# HHC.net
KiCad netlist of a schematic drawn in EAGLE
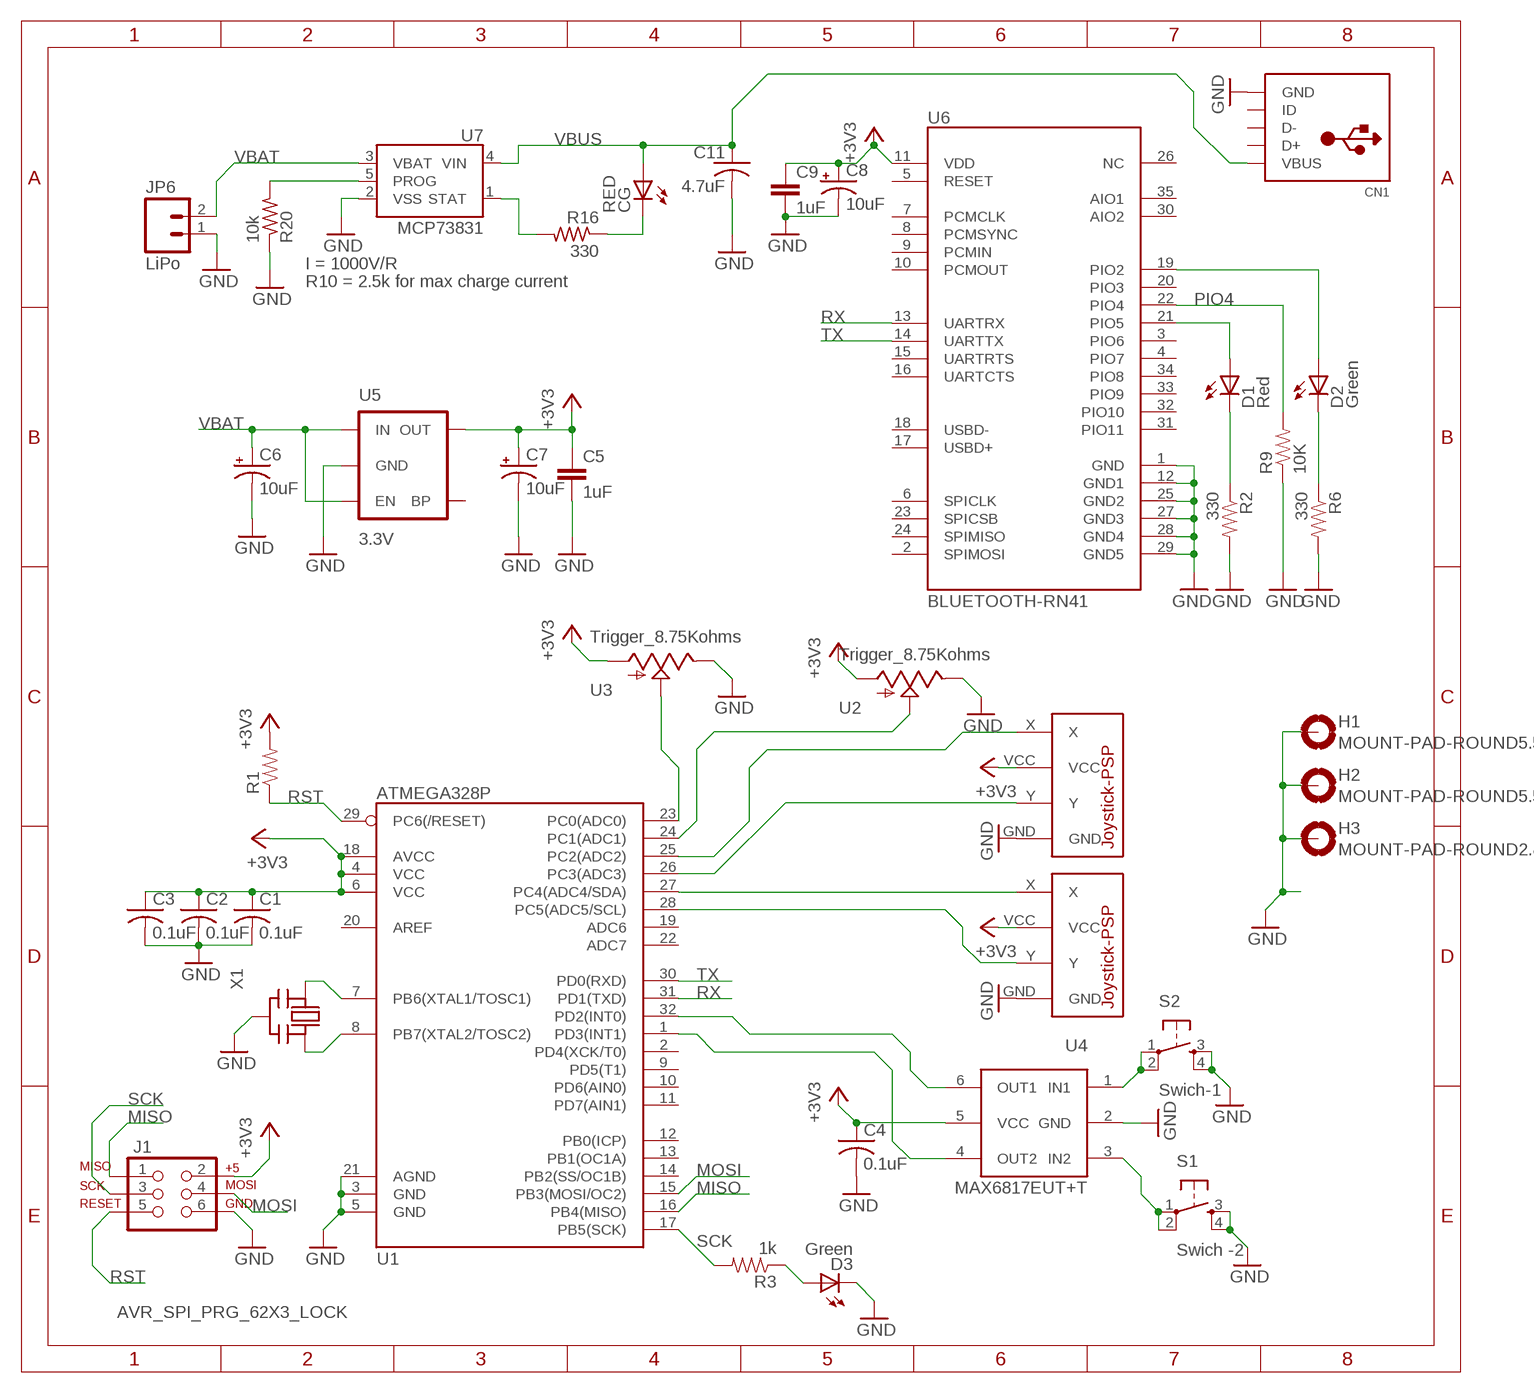
[diagram p0: schematic, sheet 1]

(export (version "E")
  (design (tool "Eeschema 10.0.6"))
  (components
    (comp (ref "C1")
      (value "0.1uF")
      (footprint "eagle-import:C0805")
      (libsource (lib "eagle-import") (part "C-USC0805"))
    )
    (comp (ref "C2")
      (value "0.1uF")
      (footprint "eagle-import:C0805")
      (libsource (lib "eagle-import") (part "C-USC0805"))
    )
    (comp (ref "C3")
      (value "0.1uF")
      (footprint "eagle-import:C0805")
      (libsource (lib "eagle-import") (part "C-USC0805"))
    )
    (comp (ref "C4")
      (value "0.1uF")
      (footprint "eagle-import:C0805")
      (libsource (lib "eagle-import") (part "C-USC0805"))
    )
    (comp (ref "C5")
      (value "1uF")
      (footprint "eagle-import:0805")
      (libsource (lib "eagle-import") (part "CAP0805"))
    )
    (comp (ref "C6")
      (value "10uF")
      (footprint "eagle-import:EIA3216")
      (libsource (lib "eagle-import") (part "CAP_POL1206"))
    )
    (comp (ref "C7")
      (value "10uF")
      (footprint "eagle-import:EIA3216")
      (libsource (lib "eagle-import") (part "CAP_POL1206"))
    )
    (comp (ref "C8")
      (value "10uF")
      (footprint "eagle-import:EIA3216")
      (libsource (lib "eagle-import") (part "CAP_POL1206"))
    )
    (comp (ref "C9")
      (value "1uF")
      (footprint "eagle-import:0805")
      (libsource (lib "eagle-import") (part "CAP0805"))
    )
    (comp (ref "C11")
      (value "4.7uF")
      (footprint "eagle-import:C0805")
      (libsource (lib "eagle-import") (part "resistor_C-USC0805"))
    )
    (comp (ref "CG")
      (value "RED")
      (footprint "eagle-import:SML0805")
      (libsource (lib "eagle-import") (part "LEDSML0805"))
    )
    (comp (ref "CN1")
      (value "USBMINIB")
      (footprint "eagle-import:USB-MINIB")
      (libsource (lib "eagle-import") (part "USBMINIB"))
    )
    (comp (ref "D1")
      (value "Red")
      (footprint "eagle-import:LED-0603")
      (libsource (lib "eagle-import") (part "LED0603"))
    )
    (comp (ref "D2")
      (value "Green")
      (footprint "eagle-import:LED-0603")
      (libsource (lib "eagle-import") (part "LED0603"))
    )
    (comp (ref "D3")
      (value "Green")
      (footprint "eagle-import:LED-0603")
      (libsource (lib "eagle-import") (part "LED0603"))
    )
    (comp (ref "H1")
      (value "MOUNT-PAD-ROUND5.5")
      (footprint "eagle-import:5,5-PAD")
      (libsource (lib "eagle-import") (part "MOUNT-PAD-ROUND5.5"))
    )
    (comp (ref "H2")
      (value "MOUNT-PAD-ROUND5.5")
      (footprint "eagle-import:5,5-PAD")
      (libsource (lib "eagle-import") (part "MOUNT-PAD-ROUND5.5"))
    )
    (comp (ref "H3")
      (value "MOUNT-PAD-ROUND2.8")
      (footprint "eagle-import:2,8-PAD")
      (libsource (lib "eagle-import") (part "MOUNT-PAD-ROUND2.8"))
    )
    (comp (ref "J1")
      (value "AVR_SPI_PRG_62X3_LOCK")
      (footprint "eagle-import:2X3_LOCK")
      (libsource (lib "eagle-import") (part "AVR_SPI_PRG_62X3_LOCK"))
    )
    (comp (ref "JP6")
      (value "LiPo")
      (footprint "eagle-import:JST-2-SMD")
      (libsource (lib "eagle-import") (part "M02-JST-2MM-SMT"))
    )
    (comp (ref "R1")
      (value "RESISTOR0805-RES")
      (footprint "eagle-import:0805")
      (libsource (lib "eagle-import") (part "SparkFun-Resistors_RESISTOR0805-RES"))
    )
    (comp (ref "R2")
      (value "330")
      (footprint "eagle-import:0805")
      (libsource (lib "eagle-import") (part "RESISTOR0805-RES"))
    )
    (comp (ref "R3")
      (value "1k")
      (footprint "eagle-import:0805")
      (libsource (lib "eagle-import") (part "SparkFun-Resistors_RESISTOR0805-RES"))
    )
    (comp (ref "R6")
      (value "330")
      (footprint "eagle-import:0805")
      (libsource (lib "eagle-import") (part "RESISTOR0805-RES"))
    )
    (comp (ref "R9")
      (value "10K")
      (footprint "eagle-import:0805")
      (libsource (lib "eagle-import") (part "RESISTOR0805-RES"))
    )
    (comp (ref "R16")
      (value "330")
      (footprint "eagle-import:R0805")
      (libsource (lib "eagle-import") (part "R-US_R0805"))
    )
    (comp (ref "R20")
      (value "10k")
      (footprint "eagle-import:R0805")
      (libsource (lib "eagle-import") (part "R-US_R0805"))
    )
    (comp (ref "S1")
      (value "Swich -2")
      (footprint "eagle-import:TACTILE-PTH")
      (libsource (lib "eagle-import") (part "TAC_SWITCHPTH"))
    )
    (comp (ref "S2")
      (value "Swich-1")
      (footprint "eagle-import:TACTILE-PTH")
      (libsource (lib "eagle-import") (part "TAC_SWITCHPTH"))
    )
    (comp (ref "U$1")
      (value "JOYSTICK-PSP1000")
      (footprint "eagle-import:JOYSTICK-PSP1000")
      (libsource (lib "eagle-import") (part "JOYSTICK-PSP1000"))
    )
    (comp (ref "U$2")
      (value "JOYSTICK-PSP1000")
      (footprint "eagle-import:JOYSTICK-PSP1000")
      (libsource (lib "eagle-import") (part "JOYSTICK-PSP1000"))
    )
    (comp (ref "U1")
      (value "ATMEGA328P")
      (footprint "eagle-import:TQFP32-08")
      (libsource (lib "eagle-import") (part "ATMEGA328_SMT"))
    )
    (comp (ref "U2")
      (value "TRIGGEREDGE_MOUNTED")
      (footprint "eagle-import:TRIGGER_EDGEMOUNT")
      (libsource (lib "eagle-import") (part "TRIGGEREDGE_MOUNTED"))
    )
    (comp (ref "U3")
      (value "TRIGGEREDGE_MOUNTED")
      (footprint "eagle-import:TRIGGER_EDGEMOUNT")
      (libsource (lib "eagle-import") (part "TRIGGEREDGE_MOUNTED"))
    )
    (comp (ref "U4")
      (value "MAX6817EUT+T")
      (footprint "eagle-import:SOT23-6")
      (libsource (lib "eagle-import") (part "MAX6817EUT+T"))
    )
    (comp (ref "U5")
      (value "3.3V")
      (footprint "eagle-import:SOT23-5")
      (libsource (lib "eagle-import") (part "V_REG_LDOSMD"))
    )
    (comp (ref "U6")
      (value "BLUETOOTH-RN41")
      (footprint "eagle-import:RN41")
      (libsource (lib "eagle-import") (part "BLUETOOTH-RN41{dblquote}"))
    )
    (comp (ref "U7")
      (value "MCP73831")
      (footprint "eagle-import:SOT23-5")
      (libsource (lib "eagle-import") (part "MCP73831"))
    )
    (comp (ref "X1")
      (value "CERMOSCILL-AWCSR")
      (footprint "eagle-import:AWCSR")
      (libsource (lib "eagle-import") (part "CERMOSCILL-AWCSR"))
    )
  )
  (nets
    (net (code "1") (name "+3V3") (class "Default")
      (node (ref "C1") (pin "1") (pinfunction "1_1") (pintype "passive"))
      (node (ref "C2") (pin "1") (pinfunction "1_1") (pintype "passive"))
      (node (ref "C3") (pin "1") (pinfunction "1_1") (pintype "passive"))
      (node (ref "C4") (pin "1") (pinfunction "1_1") (pintype "passive"))
      (node (ref "C5") (pin "1") (pinfunction "1_1") (pintype "passive"))
      (node (ref "C7") (pin "A") (pinfunction "+_A") (pintype "passive"))
      (node (ref "C8") (pin "A") (pinfunction "+_A") (pintype "passive"))
      (node (ref "C9") (pin "1") (pinfunction "1_1") (pintype "passive"))
      (node (ref "J1") (pin "2") (pinfunction "2_2") (pintype "passive"))
      (node (ref "R1") (pin "2") (pinfunction "2_2") (pintype "passive"))
      (node (ref "U$1") (pin "VCC") (pinfunction "VCC_VCC") (pintype "bidirectional"))
      (node (ref "U$2") (pin "VCC") (pinfunction "VCC_VCC") (pintype "bidirectional"))
      (node (ref "U1") (pin "18") (pinfunction "AVCC_18") (pintype "bidirectional"))
      (node (ref "U1") (pin "4") (pinfunction "VCC_4") (pintype "bidirectional"))
      (node (ref "U1") (pin "6") (pinfunction "VCC_6") (pintype "bidirectional"))
      (node (ref "U2") (pin "P$1") (pinfunction "1_P$1") (pintype "passive"))
      (node (ref "U3") (pin "P$1") (pinfunction "1_P$1") (pintype "passive"))
      (node (ref "U4") (pin "5") (pinfunction "VCC_5") (pintype "bidirectional"))
      (node (ref "U5") (pin "5") (pinfunction "OUT_5") (pintype "passive"))
      (node (ref "U6") (pin "11") (pinfunction "VDD_11") (pintype "bidirectional"))
    )
    (net (code "2") (name "/MISO") (class "Default")
      (node (ref "J1") (pin "1") (pinfunction "1_1") (pintype "passive"))
      (node (ref "U1") (pin "16") (pinfunction "PB4(MISO)_16") (pintype "bidirectional"))
    )
    (net (code "3") (name "/MOSI") (class "Default")
      (node (ref "J1") (pin "4") (pinfunction "4_4") (pintype "passive"))
      (node (ref "U1") (pin "15") (pinfunction "PB3(MOSI/OC2)_15") (pintype "bidirectional"))
    )
    (net (code "4") (name "/PIO4") (class "Default")
      (node (ref "R9") (pin "2") (pinfunction "2_2") (pintype "passive"))
      (node (ref "U6") (pin "22") (pinfunction "PIO4_22") (pintype "bidirectional"))
    )
    (net (code "5") (name "/RST") (class "Default")
      (node (ref "J1") (pin "5") (pinfunction "5_5") (pintype "passive"))
      (node (ref "R1") (pin "1") (pinfunction "1_1") (pintype "passive"))
      (node (ref "U1") (pin "29") (pinfunction "PC6(/RESET)_29") (pintype "bidirectional"))
    )
    (net (code "6") (name "/RX") (class "Default")
      (node (ref "U1") (pin "31") (pinfunction "PD1(TXD)_31") (pintype "bidirectional"))
      (node (ref "U6") (pin "13") (pinfunction "UARTRX_13") (pintype "bidirectional"))
    )
    (net (code "7") (name "/SCK") (class "Default")
      (node (ref "J1") (pin "3") (pinfunction "3_3") (pintype "passive"))
      (node (ref "R3") (pin "2") (pinfunction "2_2") (pintype "passive"))
      (node (ref "U1") (pin "17") (pinfunction "PB5(SCK)_17") (pintype "bidirectional"))
    )
    (net (code "8") (name "/TX") (class "Default")
      (node (ref "U1") (pin "30") (pinfunction "PD0(RXD)_30") (pintype "bidirectional"))
      (node (ref "U6") (pin "14") (pinfunction "UARTTX_14") (pintype "bidirectional"))
    )
    (net (code "9") (name "/VBAT") (class "Default")
      (node (ref "C6") (pin "A") (pinfunction "+_A") (pintype "passive"))
      (node (ref "JP6") (pin "2") (pinfunction "2_2") (pintype "passive"))
      (node (ref "U5") (pin "1") (pinfunction "IN_1") (pintype "input"))
      (node (ref "U5") (pin "3") (pinfunction "EN_3") (pintype "input"))
      (node (ref "U7") (pin "3") (pinfunction "VBAT_3") (pintype "power_in"))
    )
    (net (code "10") (name "/VBUS") (class "Default")
      (node (ref "C11") (pin "1") (pinfunction "1_1") (pintype "passive"))
      (node (ref "CG") (pin "A") (pinfunction "A_A") (pintype "passive"))
      (node (ref "CN1") (pin "VBUS") (pinfunction "VBUS_VBUS") (pintype "power_in"))
      (node (ref "U7") (pin "4") (pinfunction "VIN_4") (pintype "power_in"))
    )
    (net (code "11") (name "GND") (class "Default")
      (node (ref "C1") (pin "2") (pinfunction "2_2") (pintype "passive"))
      (node (ref "C11") (pin "2") (pinfunction "2_2") (pintype "passive"))
      (node (ref "C2") (pin "2") (pinfunction "2_2") (pintype "passive"))
      (node (ref "C3") (pin "2") (pinfunction "2_2") (pintype "passive"))
      (node (ref "C4") (pin "2") (pinfunction "2_2") (pintype "passive"))
      (node (ref "C5") (pin "2") (pinfunction "2_2") (pintype "passive"))
      (node (ref "C6") (pin "C") (pinfunction "-_C") (pintype "passive"))
      (node (ref "C7") (pin "C") (pinfunction "-_C") (pintype "passive"))
      (node (ref "C8") (pin "C") (pinfunction "-_C") (pintype "passive"))
      (node (ref "C9") (pin "2") (pinfunction "2_2") (pintype "passive"))
      (node (ref "CN1") (pin "GND") (pinfunction "GND_GND") (pintype "power_in"))
      (node (ref "D3") (pin "C") (pinfunction "C_C") (pintype "passive"))
      (node (ref "H1") (pin "B5,5") (pinfunction "MOUNT_B5,5") (pintype "passive"))
      (node (ref "H2") (pin "B5,5") (pinfunction "MOUNT_B5,5") (pintype "passive"))
      (node (ref "H3") (pin "B2,8") (pinfunction "MOUNT_B2,8") (pintype "passive"))
      (node (ref "J1") (pin "6") (pinfunction "6_6") (pintype "passive"))
      (node (ref "JP6") (pin "1") (pinfunction "1_1") (pintype "passive"))
      (node (ref "R2") (pin "2") (pinfunction "2_2") (pintype "passive"))
      (node (ref "R20") (pin "1") (pinfunction "1_1") (pintype "passive"))
      (node (ref "R6") (pin "2") (pinfunction "2_2") (pintype "passive"))
      (node (ref "R9") (pin "1") (pinfunction "1_1") (pintype "passive"))
      (node (ref "S1") (pin "3") (pinfunction "3_3") (pintype "passive"))
      (node (ref "S1") (pin "4") (pinfunction "4_4") (pintype "passive"))
      (node (ref "S2") (pin "3") (pinfunction "3_3") (pintype "passive"))
      (node (ref "S2") (pin "4") (pinfunction "4_4") (pintype "passive"))
      (node (ref "U$1") (pin "GND") (pinfunction "GND_GND") (pintype "bidirectional"))
      (node (ref "U$2") (pin "GND") (pinfunction "GND_GND") (pintype "bidirectional"))
      (node (ref "U1") (pin "21") (pinfunction "AGND_21") (pintype "bidirectional"))
      (node (ref "U1") (pin "3") (pinfunction "GND_3") (pintype "bidirectional"))
      (node (ref "U1") (pin "5") (pinfunction "GND_5") (pintype "bidirectional"))
      (node (ref "U2") (pin "P$3") (pinfunction "3_P$3") (pintype "passive"))
      (node (ref "U3") (pin "P$3") (pinfunction "3_P$3") (pintype "passive"))
      (node (ref "U4") (pin "2") (pinfunction "GND_2") (pintype "bidirectional"))
      (node (ref "U5") (pin "2") (pinfunction "GND_2") (pintype "input"))
      (node (ref "U6") (pin "1") (pinfunction "GND_1") (pintype "bidirectional"))
      (node (ref "U6") (pin "12") (pinfunction "GND1_12") (pintype "bidirectional"))
      (node (ref "U6") (pin "25") (pinfunction "GND2_25") (pintype "bidirectional"))
      (node (ref "U6") (pin "27") (pinfunction "GND3_27") (pintype "bidirectional"))
      (node (ref "U6") (pin "28") (pinfunction "GND4_28") (pintype "bidirectional"))
      (node (ref "U6") (pin "29") (pinfunction "GND5_29") (pintype "bidirectional"))
      (node (ref "U7") (pin "2") (pinfunction "VSS_2") (pintype "power_in"))
      (node (ref "X1") (pin "2") (pinfunction "GND_2") (pintype "bidirectional"))
    )
    (net (code "12") (name "Net-(CG-PadC)") (class "Default")
      (node (ref "CG") (pin "C") (pinfunction "C_C") (pintype "passive"))
      (node (ref "R16") (pin "1") (pinfunction "1_1") (pintype "passive"))
    )
    (net (code "13") (name "Net-(D1-PadC)") (class "Default")
      (node (ref "D1") (pin "C") (pinfunction "C_C") (pintype "passive"))
      (node (ref "R2") (pin "1") (pinfunction "1_1") (pintype "passive"))
    )
    (net (code "14") (name "Net-(D2-PadC)") (class "Default")
      (node (ref "D2") (pin "C") (pinfunction "C_C") (pintype "passive"))
      (node (ref "R6") (pin "1") (pinfunction "1_1") (pintype "passive"))
    )
    (net (code "15") (name "Net-(D3-PadA)") (class "Default")
      (node (ref "D3") (pin "A") (pinfunction "A_A") (pintype "passive"))
      (node (ref "R3") (pin "1") (pinfunction "1_1") (pintype "passive"))
    )
    (net (code "16") (name "Net-(U1-PB6(XTAL1{slash}TOSC1))") (class "Default")
      (node (ref "U1") (pin "7") (pinfunction "PB6(XTAL1/TOSC1)_7") (pintype "bidirectional"))
      (node (ref "X1") (pin "1") (pinfunction "IN_1") (pintype "bidirectional"))
    )
    (net (code "17") (name "Net-(U1-PB7(XTAL2{slash}TOSC2))") (class "Default")
      (node (ref "U1") (pin "8") (pinfunction "PB7(XTAL2/TOSC2)_8") (pintype "bidirectional"))
      (node (ref "X1") (pin "3") (pinfunction "OUT_3") (pintype "bidirectional"))
    )
    (net (code "18") (name "Net-(U1-PC0(ADC0))") (class "Default")
      (node (ref "U1") (pin "23") (pinfunction "PC0(ADC0)_23") (pintype "bidirectional"))
      (node (ref "U3") (pin "P$2") (pinfunction "2_P$2") (pintype "passive"))
    )
    (net (code "19") (name "Net-(U1-PC1(ADC1))") (class "Default")
      (node (ref "U1") (pin "24") (pinfunction "PC1(ADC1)_24") (pintype "bidirectional"))
      (node (ref "U2") (pin "P$2") (pinfunction "2_P$2") (pintype "passive"))
    )
    (net (code "20") (name "Net-(U1-PC2(ADC2))") (class "Default")
      (node (ref "U$2") (pin "X") (pinfunction "X_X") (pintype "bidirectional"))
      (node (ref "U1") (pin "25") (pinfunction "PC2(ADC2)_25") (pintype "bidirectional"))
    )
    (net (code "21") (name "Net-(U1-PC3(ADC3))") (class "Default")
      (node (ref "U$2") (pin "Y") (pinfunction "Y_Y") (pintype "bidirectional"))
      (node (ref "U1") (pin "26") (pinfunction "PC3(ADC3)_26") (pintype "bidirectional"))
    )
    (net (code "22") (name "Net-(U1-PC4(ADC4{slash}SDA))") (class "Default")
      (node (ref "U$1") (pin "X") (pinfunction "X_X") (pintype "bidirectional"))
      (node (ref "U1") (pin "27") (pinfunction "PC4(ADC4/SDA)_27") (pintype "bidirectional"))
    )
    (net (code "23") (name "Net-(U1-PC5(ADC5{slash}SCL))") (class "Default")
      (node (ref "U$1") (pin "Y") (pinfunction "Y_Y") (pintype "bidirectional"))
      (node (ref "U1") (pin "28") (pinfunction "PC5(ADC5/SCL)_28") (pintype "bidirectional"))
    )
    (net (code "24") (name "Net-(U1-PD2(INT0))") (class "Default")
      (node (ref "U1") (pin "32") (pinfunction "PD2(INT0)_32") (pintype "bidirectional"))
      (node (ref "U4") (pin "6") (pinfunction "OUT1_6") (pintype "bidirectional"))
    )
    (net (code "25") (name "Net-(U1-PD3(INT1))") (class "Default")
      (node (ref "U1") (pin "1") (pinfunction "PD3(INT1)_1") (pintype "bidirectional"))
      (node (ref "U4") (pin "4") (pinfunction "OUT2_4") (pintype "bidirectional"))
    )
    (net (code "26") (name "Net-(U4-IN1)") (class "Default")
      (node (ref "S2") (pin "1") (pinfunction "1_1") (pintype "passive"))
      (node (ref "S2") (pin "2") (pinfunction "2_2") (pintype "passive"))
      (node (ref "U4") (pin "1") (pinfunction "IN1_1") (pintype "bidirectional"))
    )
    (net (code "27") (name "Net-(U4-IN2)") (class "Default")
      (node (ref "S1") (pin "1") (pinfunction "1_1") (pintype "passive"))
      (node (ref "S1") (pin "2") (pinfunction "2_2") (pintype "passive"))
      (node (ref "U4") (pin "3") (pinfunction "IN2_3") (pintype "bidirectional"))
    )
    (net (code "28") (name "Net-(U6-PIO2)") (class "Default")
      (node (ref "D2") (pin "A") (pinfunction "A_A") (pintype "passive"))
      (node (ref "U6") (pin "19") (pinfunction "PIO2_19") (pintype "bidirectional"))
    )
    (net (code "29") (name "Net-(U6-PIO5)") (class "Default")
      (node (ref "D1") (pin "A") (pinfunction "A_A") (pintype "passive"))
      (node (ref "U6") (pin "21") (pinfunction "PIO5_21") (pintype "bidirectional"))
    )
    (net (code "30") (name "Net-(U7-PROG)") (class "Default")
      (node (ref "R20") (pin "2") (pinfunction "2_2") (pintype "passive"))
      (node (ref "U7") (pin "5") (pinfunction "PROG_5") (pintype "input"))
    )
    (net (code "31") (name "Net-(U7-STAT)") (class "Default")
      (node (ref "R16") (pin "2") (pinfunction "2_2") (pintype "passive"))
      (node (ref "U7") (pin "1") (pinfunction "STAT_1") (pintype "output"))
    )
    (net (code "32") (name "unconnected-(CN1-PadD+)") (class "Default")
      (node (ref "CN1") (pin "D+") (pinfunction "D+_D+") (pintype "bidirectional"))
    )
    (net (code "33") (name "unconnected-(CN1-PadD-)") (class "Default")
      (node (ref "CN1") (pin "D-") (pinfunction "D-_D-") (pintype "bidirectional"))
    )
    (net (code "34") (name "unconnected-(CN1-PadID)") (class "Default")
      (node (ref "CN1") (pin "ID") (pinfunction "ID_ID") (pintype "bidirectional"))
    )
    (net (code "35") (name "unconnected-(U1-ADC6-Pad19)") (class "Default")
      (node (ref "U1") (pin "19") (pinfunction "ADC6_19") (pintype "bidirectional"))
    )
    (net (code "36") (name "unconnected-(U1-ADC7-Pad22)") (class "Default")
      (node (ref "U1") (pin "22") (pinfunction "ADC7_22") (pintype "bidirectional"))
    )
    (net (code "37") (name "unconnected-(U1-AREF-Pad20)") (class "Default")
      (node (ref "U1") (pin "20") (pinfunction "AREF_20") (pintype "bidirectional"))
    )
    (net (code "38") (name "unconnected-(U1-PB0(ICP)-Pad12)") (class "Default")
      (node (ref "U1") (pin "12") (pinfunction "PB0(ICP)_12") (pintype "bidirectional"))
    )
    (net (code "39") (name "unconnected-(U1-PB1(OC1A)-Pad13)") (class "Default")
      (node (ref "U1") (pin "13") (pinfunction "PB1(OC1A)_13") (pintype "bidirectional"))
    )
    (net (code "40") (name "unconnected-(U1-PB2(SS{slash}OC1B)-Pad14)") (class "Default")
      (node (ref "U1") (pin "14") (pinfunction "PB2(SS/OC1B)_14") (pintype "bidirectional"))
    )
    (net (code "41") (name "unconnected-(U1-PD4(XCK{slash}T0)-Pad2)") (class "Default")
      (node (ref "U1") (pin "2") (pinfunction "PD4(XCK/T0)_2") (pintype "bidirectional"))
    )
    (net (code "42") (name "unconnected-(U1-PD5(T1)-Pad9)") (class "Default")
      (node (ref "U1") (pin "9") (pinfunction "PD5(T1)_9") (pintype "bidirectional"))
    )
    (net (code "43") (name "unconnected-(U1-PD6(AIN0)-Pad10)") (class "Default")
      (node (ref "U1") (pin "10") (pinfunction "PD6(AIN0)_10") (pintype "bidirectional"))
    )
    (net (code "44") (name "unconnected-(U1-PD7(AIN1)-Pad11)") (class "Default")
      (node (ref "U1") (pin "11") (pinfunction "PD7(AIN1)_11") (pintype "bidirectional"))
    )
    (net (code "45") (name "unconnected-(U5-BP-Pad4)") (class "Default")
      (node (ref "U5") (pin "4") (pinfunction "BP_4") (pintype "input"))
    )
    (net (code "46") (name "unconnected-(U6-AIO1-Pad35)") (class "Default")
      (node (ref "U6") (pin "35") (pinfunction "AIO1_35") (pintype "bidirectional"))
    )
    (net (code "47") (name "unconnected-(U6-AIO2-Pad30)") (class "Default")
      (node (ref "U6") (pin "30") (pinfunction "AIO2_30") (pintype "bidirectional"))
    )
    (net (code "48") (name "unconnected-(U6-NC-Pad26)") (class "Default")
      (node (ref "U6") (pin "26") (pinfunction "NC_26") (pintype "bidirectional"))
    )
    (net (code "49") (name "unconnected-(U6-PCMCLK-Pad7)") (class "Default")
      (node (ref "U6") (pin "7") (pinfunction "PCMCLK_7") (pintype "bidirectional"))
    )
    (net (code "50") (name "unconnected-(U6-PCMIN-Pad9)") (class "Default")
      (node (ref "U6") (pin "9") (pinfunction "PCMIN_9") (pintype "bidirectional"))
    )
    (net (code "51") (name "unconnected-(U6-PCMOUT-Pad10)") (class "Default")
      (node (ref "U6") (pin "10") (pinfunction "PCMOUT_10") (pintype "bidirectional"))
    )
    (net (code "52") (name "unconnected-(U6-PCMSYNC-Pad8)") (class "Default")
      (node (ref "U6") (pin "8") (pinfunction "PCMSYNC_8") (pintype "bidirectional"))
    )
    (net (code "53") (name "unconnected-(U6-PIO3-Pad20)") (class "Default")
      (node (ref "U6") (pin "20") (pinfunction "PIO3_20") (pintype "bidirectional"))
    )
    (net (code "54") (name "unconnected-(U6-PIO6-Pad3)") (class "Default")
      (node (ref "U6") (pin "3") (pinfunction "PIO6_3") (pintype "bidirectional"))
    )
    (net (code "55") (name "unconnected-(U6-PIO7-Pad4)") (class "Default")
      (node (ref "U6") (pin "4") (pinfunction "PIO7_4") (pintype "bidirectional"))
    )
    (net (code "56") (name "unconnected-(U6-PIO8-Pad34)") (class "Default")
      (node (ref "U6") (pin "34") (pinfunction "PIO8_34") (pintype "bidirectional"))
    )
    (net (code "57") (name "unconnected-(U6-PIO9-Pad33)") (class "Default")
      (node (ref "U6") (pin "33") (pinfunction "PIO9_33") (pintype "bidirectional"))
    )
    (net (code "58") (name "unconnected-(U6-PIO10-Pad32)") (class "Default")
      (node (ref "U6") (pin "32") (pinfunction "PIO10_32") (pintype "bidirectional"))
    )
    (net (code "59") (name "unconnected-(U6-PIO11-Pad31)") (class "Default")
      (node (ref "U6") (pin "31") (pinfunction "PIO11_31") (pintype "bidirectional"))
    )
    (net (code "60") (name "unconnected-(U6-RESET-Pad5)") (class "Default")
      (node (ref "U6") (pin "5") (pinfunction "RESET_5") (pintype "bidirectional"))
    )
    (net (code "61") (name "unconnected-(U6-SPICLK-Pad6)") (class "Default")
      (node (ref "U6") (pin "6") (pinfunction "SPICLK_6") (pintype "bidirectional"))
    )
    (net (code "62") (name "unconnected-(U6-SPICSB-Pad23)") (class "Default")
      (node (ref "U6") (pin "23") (pinfunction "SPICSB_23") (pintype "bidirectional"))
    )
    (net (code "63") (name "unconnected-(U6-SPIMISO-Pad24)") (class "Default")
      (node (ref "U6") (pin "24") (pinfunction "SPIMISO_24") (pintype "bidirectional"))
    )
    (net (code "64") (name "unconnected-(U6-SPIMOSI-Pad2)") (class "Default")
      (node (ref "U6") (pin "2") (pinfunction "SPIMOSI_2") (pintype "bidirectional"))
    )
    (net (code "65") (name "unconnected-(U6-UARTCTS-Pad16)") (class "Default")
      (node (ref "U6") (pin "16") (pinfunction "UARTCTS_16") (pintype "bidirectional"))
    )
    (net (code "66") (name "unconnected-(U6-UARTRTS-Pad15)") (class "Default")
      (node (ref "U6") (pin "15") (pinfunction "UARTRTS_15") (pintype "bidirectional"))
    )
    (net (code "67") (name "unconnected-(U6-USBD+-Pad17)") (class "Default")
      (node (ref "U6") (pin "17") (pinfunction "USBD+_17") (pintype "bidirectional"))
    )
    (net (code "68") (name "unconnected-(U6-USBD--Pad18)") (class "Default")
      (node (ref "U6") (pin "18") (pinfunction "USBD-_18") (pintype "bidirectional"))
    )
  )
)
